# new.net
KiCad netlist of a schematic drawn in EAGLE
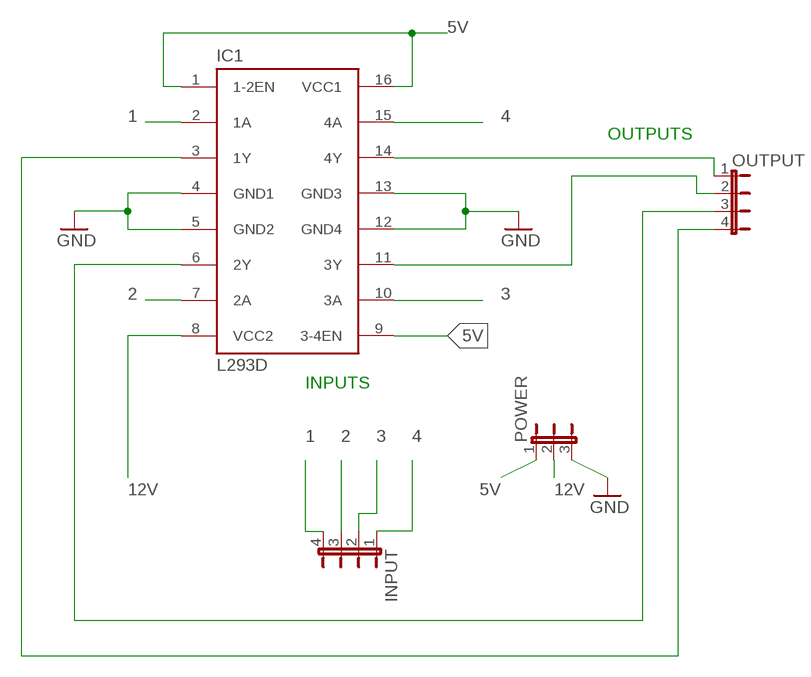
[diagram p0: schematic, sheet 1]

(export (version "E")
  (design (tool "Eeschema 10.0.6"))
  (components
    (comp (ref "IC1")
      (value "L293D")
      (footprint "eagle-import:DIL16")
      (libsource (lib "eagle-import") (part "L293D"))
    )
    (comp (ref "INPUT")
      (value "JP4E")
      (footprint "eagle-import:JP4")
      (libsource (lib "eagle-import") (part "JP4E"))
    )
    (comp (ref "OUTPUT")
      (value "JP4E")
      (footprint "eagle-import:JP4")
      (libsource (lib "eagle-import") (part "JP4E"))
    )
    (comp (ref "POWER")
      (value "JP2E")
      (footprint "eagle-import:JP2")
      (libsource (lib "eagle-import") (part "JP2E"))
    )
  )
  (nets
    (net (code "1") (name "/1") (class "Default")
      (node (ref "IC1") (pin "2") (pinfunction "1A_2") (pintype "input"))
      (node (ref "INPUT") (pin "4") (pinfunction "4_4") (pintype "passive"))
    )
    (net (code "2") (name "/2") (class "Default")
      (node (ref "IC1") (pin "7") (pinfunction "2A_7") (pintype "input"))
      (node (ref "INPUT") (pin "3") (pinfunction "3_3") (pintype "passive"))
    )
    (net (code "3") (name "/3") (class "Default")
      (node (ref "IC1") (pin "10") (pinfunction "3A_10") (pintype "input"))
      (node (ref "INPUT") (pin "2") (pinfunction "2_2") (pintype "passive"))
    )
    (net (code "4") (name "/4") (class "Default")
      (node (ref "IC1") (pin "15") (pinfunction "4A_15") (pintype "input"))
      (node (ref "INPUT") (pin "1") (pinfunction "1_1") (pintype "passive"))
    )
    (net (code "5") (name "/12V") (class "Default")
      (node (ref "IC1") (pin "8") (pinfunction "VCC2_8") (pintype "power_in"))
      (node (ref "POWER") (pin "2") (pinfunction "2_2") (pintype "passive"))
    )
    (net (code "6") (name "5V") (class "Default")
      (node (ref "IC1") (pin "1") (pinfunction "1-2EN_1") (pintype "input"))
      (node (ref "IC1") (pin "16") (pinfunction "VCC1_16") (pintype "power_in"))
      (node (ref "IC1") (pin "9") (pinfunction "3-4EN_9") (pintype "input"))
      (node (ref "POWER") (pin "1") (pinfunction "1_1") (pintype "passive"))
    )
    (net (code "7") (name "GND") (class "Default")
      (node (ref "IC1") (pin "12") (pinfunction "GND4_12") (pintype "power_in"))
      (node (ref "IC1") (pin "13") (pinfunction "GND3_13") (pintype "power_in"))
      (node (ref "IC1") (pin "4") (pinfunction "GND1_4") (pintype "power_in"))
      (node (ref "IC1") (pin "5") (pinfunction "GND2_5") (pintype "power_in"))
      (node (ref "POWER") (pin "3") (pinfunction "3_3") (pintype "passive"))
    )
    (net (code "8") (name "Net-(IC1-1Y)") (class "Default")
      (node (ref "IC1") (pin "3") (pinfunction "1Y_3") (pintype "output"))
      (node (ref "OUTPUT") (pin "4") (pinfunction "4_4") (pintype "passive"))
    )
    (net (code "9") (name "Net-(IC1-2Y)") (class "Default")
      (node (ref "IC1") (pin "6") (pinfunction "2Y_6") (pintype "output"))
      (node (ref "OUTPUT") (pin "3") (pinfunction "3_3") (pintype "passive"))
    )
    (net (code "10") (name "Net-(IC1-3Y)") (class "Default")
      (node (ref "IC1") (pin "11") (pinfunction "3Y_11") (pintype "output"))
      (node (ref "OUTPUT") (pin "2") (pinfunction "2_2") (pintype "passive"))
    )
    (net (code "11") (name "Net-(IC1-4Y)") (class "Default")
      (node (ref "IC1") (pin "14") (pinfunction "4Y_14") (pintype "output"))
      (node (ref "OUTPUT") (pin "1") (pinfunction "1_1") (pintype "passive"))
    )
  )
)
